# PowerSupply.net
KiCad netlist of a schematic drawn in Altium Designer
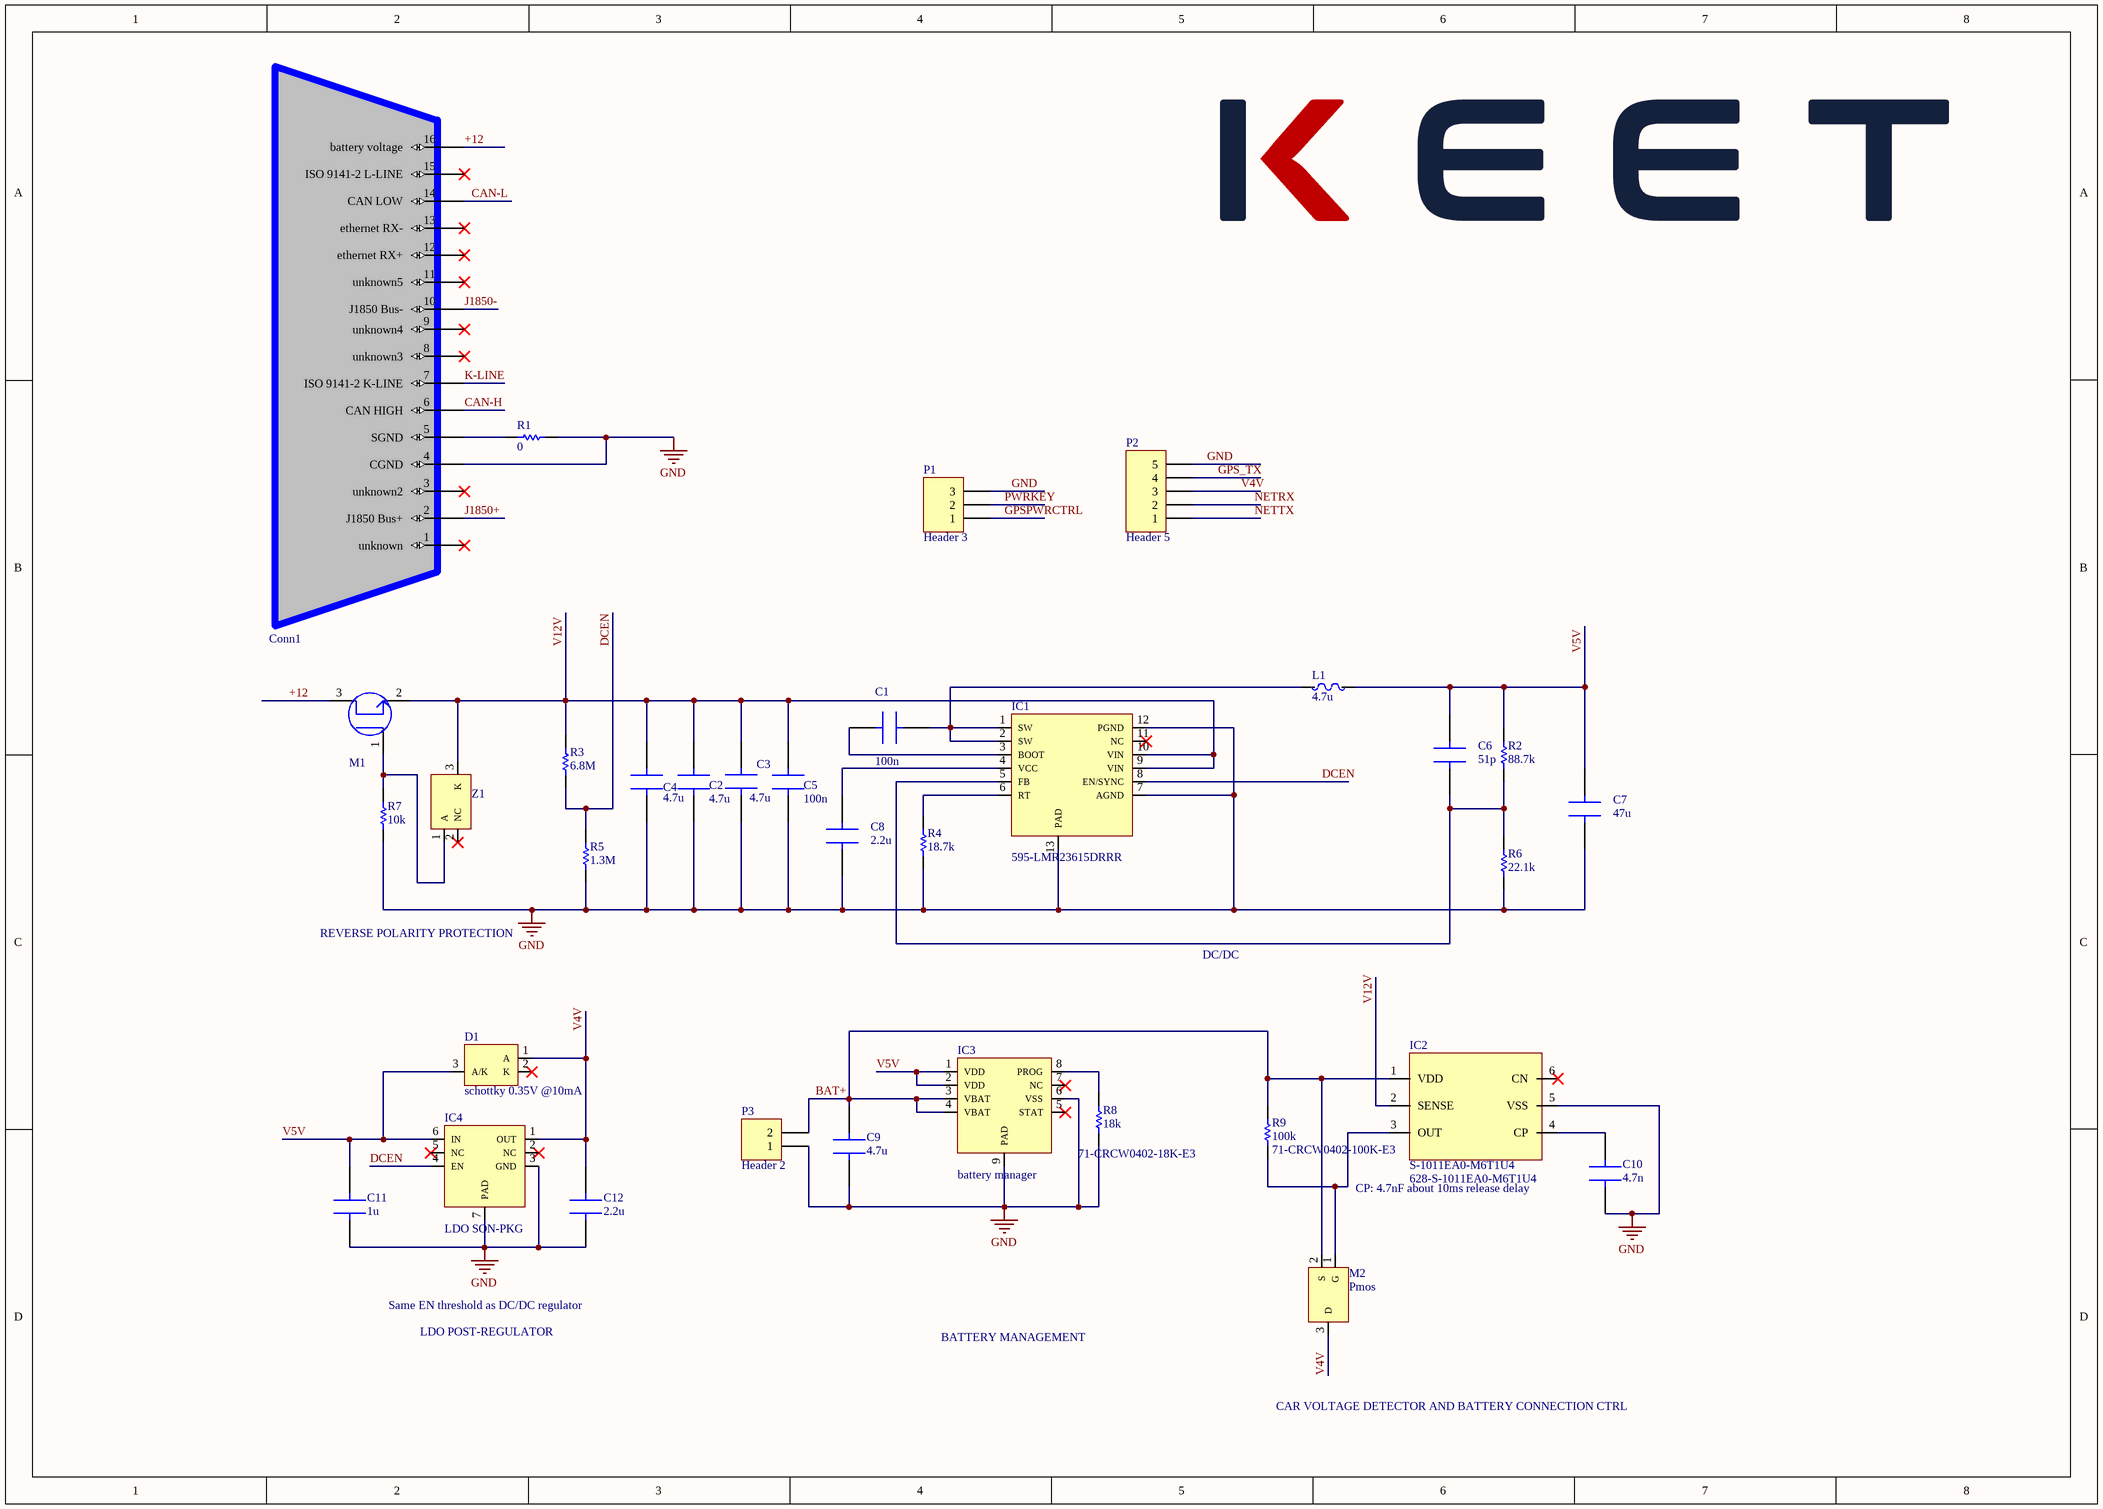
[diagram p0: PowerSupply.SchDoc]

(export (version "E")
  (design (tool "Eeschema 10.0.6"))
  (components
    (comp (ref "C1")
      (value "100n")
      (footprint "CAPC1005X06N")
      (description "CAP CER 0.1UF 16V X7R 0402")
      (fields
        (field (name "MANUFACTURER") "Murata")
        (field (name "MANUFACTURER PART NUMBER") "GRM155R71C104KA88D")
      )
      (libsource (lib "KeetV2") (part "GRM155R71C104KA88D"))
    )
    (comp (ref "C2")
      (value "4.7u")
      (footprint "CAPC1608X10N")
      (description "Cap Ceramic 4.7uF 25V X5R 20% SMD 0603 85°C Paper T/R")
      (fields
        (field (name "MANUFACTURER") "Taiyo Yuden")
        (field (name "MANUFACTURER PART NUMBER") "TMK107BBJ475MA-T")
      )
      (libsource (lib "KeetV2") (part "TMK107BBJ475MA-T"))
    )
    (comp (ref "C3")
      (value "4.7u")
      (footprint "CAPC1608X10N")
      (description "Cap Ceramic 4.7uF 25V X5R 20% SMD 0603 85°C Paper T/R")
      (fields
        (field (name "MANUFACTURER") "Taiyo Yuden")
        (field (name "MANUFACTURER PART NUMBER") "TMK107BBJ475MA-T")
      )
      (libsource (lib "KeetV2") (part "TMK107BBJ475MA-T"))
    )
    (comp (ref "C4")
      (value "4.7u")
      (footprint "CAPC1608X10N")
      (description "Cap Ceramic 4.7uF 25V X5R 20% SMD 0603 85°C Paper T/R")
      (fields
        (field (name "MANUFACTURER") "Taiyo Yuden")
        (field (name "MANUFACTURER PART NUMBER") "TMK107BBJ475MA-T")
      )
      (libsource (lib "KeetV2") (part "TMK107BBJ475MA-T"))
    )
    (comp (ref "C5")
      (value "100n")
      (footprint "CAPC1005X06N")
      (description "CAP CER 0.1UF 50V X5R 0402")
      (fields
        (field (name "MANUFACTURER") "TDK")
        (field (name "MANUFACTURER PART NUMBER") "C1005X5R1H104K050BB")
      )
      (libsource (lib "KeetV2") (part "C1005X5R1H104K050BB"))
    )
    (comp (ref "C6")
      (value "51p")
      (footprint "CAPC1005X06N")
      (description "CAP CER 51PF 50V C0G/NP0 0402")
      (fields
        (field (name "MANUFACTURER") "Murata")
        (field (name "MANUFACTURER PART NUMBER") "GRM1555C1H510JA01D")
      )
      (libsource (lib "KeetV2") (part "GRM1555C1H510JA01D"))
    )
    (comp (ref "C7")
      (value "47u")
      (footprint "CAPC3216X12N")
      (description "Multilayer Ceramic Capacitors MLCC - SMD/SMT 1206 47uF 10Vdc X5R +/-10%")
      (fields
        (field (name "MANUFACTURER") "Murata")
        (field (name "MANUFACTURER PART NUMBER") "GRM31CR61A476KE15L")
      )
      (libsource (lib "KeetV2") (part "GRM31CR61A476KE15L"))
    )
    (comp (ref "C8")
      (value "2.2u")
      (footprint "CAPC1608X10N")
      (fields
        (field (name "MANUFACTURER") "Samsung")
        (field (name "MANUFACTURER PART NUMBER") "CL10A225KP8NNNC")
        (field (name "TOLERANCE") "10%")
      )
      (libsource (lib "KeetV2") (part "CL10A225KP8NNNC"))
    )
    (comp (ref "C9")
      (value "4.7u")
      (footprint "CAPC1005X06N")
      (fields
        (field (name "MANUFACTURER") "Murata")
        (field (name "MANUFACTURER PART NUMBER") "GRM155R60J475ME87D")
        (field (name "TOLERANCE") "20%")
      )
      (libsource (lib "KeetV2") (part "GRM155R60J475ME87D"))
    )
    (comp (ref "C10")
      (value "4.7n")
      (footprint "CAPC1005X06N")
      (description "Multilayer Ceramic Capacitors MLCC - SMD/SMT")
      (fields
        (field (name "MANUFACTURER") "Murata")
        (field (name "MANUFACTURER PART NUMBER") "GRM155R71H472JA01J")
      )
      (libsource (lib "KeetV2") (part "GRM155R71H472JA01J"))
    )
    (comp (ref "C11")
      (value "1u")
      (footprint "CAPC1005X06N")
      (description "TAIYO YUDEN - EMK105BJ105KVHF - CAPACITOR,CERAMIC,0402,16V,X5R,1 F, 10% ROHS COMPLIANT: YES")
      (fields
        (field (name "MANUFACTURER") "Taiyo Yuden")
        (field (name "MANUFACTURER PART NUMBER") "EMK105BJ105KVHF")
      )
      (libsource (lib "KeetV2") (part "EMK105BJ105KVHF"))
    )
    (comp (ref "C12")
      (value "2.2u")
      (footprint "CAPC1005X06N")
      (description "Multilayer Ceramic Capacitor 2.2uF 25V 10% 0402 Paper T/R")
      (fields
        (field (name "MANUFACTURER") "Taiyo Yuden")
        (field (name "MANUFACTURER PART NUMBER") "TMK105CBJ225KV-F")
      )
      (libsource (lib "KeetV2") (part "TMK105CBJ225KV-F"))
    )
    (comp (ref "Conn1")
      (value "OBD2 connector")
      (footprint "OBD2")
      (libsource (lib "KeetV2") (part "OBD2 connector"))
    )
    (comp (ref "D1")
      (value "schottky 0.35V @10mA")
      (footprint "SOT95P245X110-3N")
      (description "Diode Schottky 30V 0.2A 3-Pin SOT-23 T/R")
      (fields
        (field (name "MANUFACTURER") "ON Semiconductor")
        (field (name "MANUFACTURER PART NUMBER") "BAT54CLT1G")
      )
      (libsource (lib "KeetV2") (part "BAT54CLT1G"))
    )
    (comp (ref "IC1")
      (value "DC/DC")
      (footprint "SON50P300X80_HS-13N")
      (description "SIMPLE SWITCHER®, 36-V, 1.5-A Synchronous Step-Down Converter 12-SON -40 to 125")
      (fields
        (field (name "MANUFACTURER") "Texas Instruments")
        (field (name "MANUFACTURER PART NUMBER") "LMR23615DRRR")
        (field (name "SUPPLIER PART NUMBER 1") "595-LMR23615DRRR")
      )
      (libsource (lib "KeetV2") (part "LMR23615DRRR"))
    )
    (comp (ref "IC2")
      (value "S-1011EA0-M6T1U4")
      (footprint "SOT95P245X110-6N")
      (description "Voltage detector")
      (fields
        (field (name "MANUFACTURER") "ABLIC U.S.A.")
        (field (name "SUPPLIER PART NUMBER 1") "628-S-1011EA0-M6T1U4")
      )
      (libsource (lib "KeetV2") (part "S-1011EA0-M6T1U4"))
    )
    (comp (ref "IC3")
      (value "battery manager")
      (footprint "PSON50P300X100_HS-9N")
      (description "IC CONTROLLER LI-ION 4.2V 8DFN")
      (fields
        (field (name "MANUFACTURER") "Microchip")
        (field (name "MANUFACTURER PART NUMBER") "MCP73831T-2ACI/MC")
      )
      (libsource (lib "KeetV2") (part "MCP73831T-2ACI/MC"))
    )
    (comp (ref "IC4")
      (value "LDO SON-PKG")
      (footprint "SON65P200X80_HS-7N")
      (description "1-A, low-IQ, high-accuracy, low-dropout voltage regulator with enable 6-WSON -40 to 125")
      (fields
        (field (name "MANUFACTURER") "Texas Instruments")
        (field (name "MANUFACTURER PART NUMBER") "TLV75740PDRVR")
      )
      (libsource (lib "KeetV2") (part "TLV75740PDRVR"))
    )
    (comp (ref "L1")
      (value "4.7u")
      (footprint "INDC4040X19N")
      (description "Inductor Power Shielded Wirewound 4.7uH 20% 100KHz 2.2A 90mOhm DCR 1515 T/R")
      (fields
        (field (name "MANUFACTURER") "Vishay Dale")
        (field (name "MANUFACTURER PART NUMBER") "IFSC1515AHER4R7M01")
      )
      (libsource (lib "KeetV2") (part "IFSC1515AHER4R7M01"))
    )
    (comp (ref "M1")
      (value "Pmos enhancement")
      (footprint "SOT95P245X110-3N")
      (description "DMPH6250SQ Series 60 V 2.4 A P-Channel Enhancement Mode Mosfet - SOT-23-3")
      (fields (field (name "MANUFACTURER") "Diodes") (field (name "MANUFACTURER PART NUMBER") "DMPH6250SQ-7"))
      (libsource (lib "KeetV2") (part "DMPH6250SQ-7"))
    )
    (comp (ref "M2")
      (value "Pmos")
      (footprint "SOT95P245X110-3N")
      (description "P-Channel 12 V 31 mOhm Surface Mount Enhancement Mode Mosfet - SOT-23-3")
      (fields (field (name "MANUFACTURER") "Diodes") (field (name "MANUFACTURER PART NUMBER") "DMP1045U-7"))
      (libsource (lib "KeetV2") (part "DMP1045U-7"))
    )
    (comp (ref "P1")
      (value "Header 3")
      (footprint "HDR1X3")
      (description "Header, 3-Pin")
      (fields (field (name "PUBLISHER") "Altium Limited"))
      (libsource (lib "Miscellaneous Connectors") (part "Header 3"))
    )
    (comp (ref "P2")
      (value "Header 5")
      (footprint "HDR1X5")
      (description "Header, 5-Pin")
      (fields (field (name "PUBLISHER") "Altium Limited"))
      (libsource (lib "Miscellaneous Connectors") (part "Header 5"))
    )
    (comp (ref "P3")
      (value "Header 2")
      (footprint "HDR1X2")
      (description "Header, 2-Pin")
      (fields (field (name "PUBLISHER") "Altium Limited"))
      (libsource (lib "Miscellaneous Connectors") (part "Header 2"))
    )
    (comp (ref "R1")
      (value "0")
      (footprint "RESC1608X04N")
      (description "YAGEO - RC0603JR-130RL - RES, THICK FILM, 0R, 0.1W, 0603")
      (fields
        (field (name "MANUFACTURER") "Yageo")
        (field (name "MANUFACTURER PART NUMBER") "RC0603JR-130RL")
      )
      (libsource (lib "KeetV2") (part "RC0603JR-130RL"))
    )
    (comp (ref "R2")
      (value "88.7k")
      (footprint "RESC1005X04N")
      (description "Res Thick Film 0402 88.7K Ohm 1% 0.063W(1/16W) ±100ppm/C Molded SMD Paper Tape on Plastic Reel")
      (fields
        (field (name "MANUFACTURER") "Bourns")
        (field (name "MANUFACTURER PART NUMBER") "CR0402-FX-8872GLF")
      )
      (libsource (lib "KeetV2") (part "CR0402-FX-8872GLF"))
    )
    (comp (ref "R3")
      (value "6.8M")
      (footprint "RESC1005X04N")
      (fields
        (field (name "MANUFACTURER") "Vishay")
        (field (name "MANUFACTURER PART NUMBER") "CRCW04026M80FKED")
        (field (name "TOLERANCE") "1%")
      )
      (libsource (lib "KeetV2") (part "CRCW04026M80FKED"))
    )
    (comp (ref "R4")
      (value "18.7k")
      (footprint "RESC1005X04N")
      (description "RES SMD 18.7K OHM 1% 1/16W 0402")
      (fields
        (field (name "MANUFACTURER") "Bourns")
        (field (name "MANUFACTURER PART NUMBER") "CR0402-FX-1872GLF")
      )
      (libsource (lib "KeetV2") (part "CR0402-FX-1872GLF"))
    )
    (comp (ref "R5")
      (value "1.3M")
      (footprint "RESC1005X04N")
      (description "RES SMD 1.3M OHM 1% 1/16W 0402")
      (fields
        (field (name "MANUFACTURER") "Yageo")
        (field (name "MANUFACTURER PART NUMBER") "AC0402FR-071M3L")
      )
      (libsource (lib "KeetV2") (part "AC0402FR-071M3L"))
    )
    (comp (ref "R6")
      (value "22.1k")
      (footprint "RESC1005X04N")
      (description "Resistor;  Thick Film;  22.1 Kilohms;  0.063 W;  1%;  SMT;  0402;  TCR 37 ppm/DegC;  TR")
      (fields
        (field (name "MANUFACTURER") "Vishay")
        (field (name "MANUFACTURER PART NUMBER") "CRCW040222K1FKED")
      )
      (libsource (lib "KeetV2") (part "CRCW040222K1FKED"))
    )
    (comp (ref "R7")
      (value "10k")
      (footprint "RESC1005X04N")
      (description "Res Thick Film 0402 10K Ohm 1% 1/16W ±100ppm/°C Molded SMD Paper T/R")
      (fields
        (field (name "MANUFACTURER") "Vishay")
        (field (name "MANUFACTURER PART NUMBER") "CRCW0402-10K0FKED")
      )
      (libsource (lib "KeetV2") (part "CRCW0402-10K0FKED"))
    )
    (comp (ref "R8")
      (value "18k")
      (footprint "RESC1005X04N")
      (fields
        (field (name "MANUFACTURER") "Vishay")
        (field (name "MANUFACTURER PART NUMBER") "CRCW040218K0FKED")
        (field (name "TOLERANCE") "1%")
        (field (name "SUPPLIER PART NUMBER 1") "71-CRCW0402-18K-E3")
      )
      (libsource (lib "KeetV2") (part "CRCW040218K0FKED"))
    )
    (comp (ref "R9")
      (value "100k")
      (footprint "RESC1005X04N")
      (description "Res Thick Film 0402 100K Ohm 1% 1/16W 100ppm/C Molded SMD Paper T/R")
      (fields
        (field (name "MANUFACTURER") "Vishay")
        (field (name "MANUFACTURER PART NUMBER") "CRCW0402100KFKED")
        (field (name "SUPPLIER PART NUMBER 1") "71-CRCW0402-100K-E3")
      )
      (libsource (lib "KeetV2") (part "CRCW0402100KFKED"))
    )
    (comp (ref "Z1")
      (value "zener 10V")
      (footprint "SOT95P245X110-3N")
      (description "ON SEMICONDUCTOR - BZX84C10LT1G - Zener Single Diode, 10 V, 225 mW, SOT-23, 6 %, 3 Pins, 150 °C")
      (fields
        (field (name "MANUFACTURER") "ON Semiconductor")
        (field (name "MANUFACTURER PART NUMBER") "BZX84C10LT1G")
      )
      (libsource (lib "KeetV2") (part "BZX84C10LT1G"))
    )
  )
  (nets
    (net (code "1") (name "/+12") (class "Default")
      (node (ref "Conn1") (pin "16") (pinfunction "battery_voltage_16") (pintype "bidirectional"))
      (node (ref "M1") (pin "3") (pinfunction "3_3") (pintype "passive"))
    )
    (net (code "2") (name "/BAT+") (class "Default")
      (node (ref "C9") (pin "2") (pinfunction "2_2") (pintype "passive"))
      (node (ref "IC2") (pin "1") (pinfunction "VDD_1") (pintype "passive"))
      (node (ref "IC3") (pin "3") (pinfunction "VBAT_3") (pintype "passive"))
      (node (ref "IC3") (pin "4") (pinfunction "VBAT_4") (pintype "passive"))
      (node (ref "M2") (pin "2") (pinfunction "S_2") (pintype "passive"))
      (node (ref "P3") (pin "2") (pinfunction "2_2") (pintype "passive"))
      (node (ref "R9") (pin "1") (pinfunction "1_1") (pintype "passive"))
    )
    (net (code "3") (name "/CAN-H") (class "Default")
      (node (ref "Conn1") (pin "6") (pinfunction "CAN_HIGH_6") (pintype "bidirectional"))
    )
    (net (code "4") (name "/CAN-L") (class "Default")
      (node (ref "Conn1") (pin "14") (pinfunction "CAN_LOW_14") (pintype "bidirectional"))
    )
    (net (code "5") (name "/DCEN") (class "Default")
      (node (ref "IC1") (pin "8") (pinfunction "EN/SYNC_8") (pintype "passive"))
      (node (ref "IC4") (pin "4") (pinfunction "EN_4") (pintype "passive"))
      (node (ref "R3") (pin "1") (pinfunction "1_1") (pintype "passive"))
      (node (ref "R5") (pin "2") (pinfunction "2_2") (pintype "passive"))
    )
    (net (code "6") (name "/GPSPWRCTRL") (class "Default")
      (node (ref "P1") (pin "1") (pinfunction "1_1") (pintype "passive"))
    )
    (net (code "7") (name "/GPS_TX") (class "Default")
      (node (ref "P2") (pin "4") (pinfunction "4_4") (pintype "passive"))
    )
    (net (code "8") (name "/J1850+") (class "Default")
      (node (ref "Conn1") (pin "2") (pinfunction "J1850_Bus+_2") (pintype "bidirectional"))
    )
    (net (code "9") (name "/J1850-") (class "Default")
      (node (ref "Conn1") (pin "10") (pinfunction "J1850_Bus-_10") (pintype "bidirectional"))
    )
    (net (code "10") (name "/K-LINE") (class "Default")
      (node (ref "Conn1") (pin "7") (pinfunction "ISO_9141-2_K-LINE_7") (pintype "bidirectional"))
    )
    (net (code "11") (name "/NETRX") (class "Default")
      (node (ref "P2") (pin "2") (pinfunction "2_2") (pintype "passive"))
    )
    (net (code "12") (name "/NETTX") (class "Default")
      (node (ref "P2") (pin "1") (pinfunction "1_1") (pintype "passive"))
    )
    (net (code "13") (name "/PWRKEY") (class "Default")
      (node (ref "P1") (pin "2") (pinfunction "2_2") (pintype "passive"))
    )
    (net (code "14") (name "/V4V") (class "Default")
      (node (ref "C12") (pin "1") (pinfunction "1_1") (pintype "passive"))
      (node (ref "D1") (pin "1") (pinfunction "A_1") (pintype "passive"))
      (node (ref "IC4") (pin "1") (pinfunction "OUT_1") (pintype "passive"))
      (node (ref "M2") (pin "3") (pinfunction "D_3") (pintype "passive"))
      (node (ref "P2") (pin "3") (pinfunction "3_3") (pintype "passive"))
    )
    (net (code "15") (name "/V5V") (class "Default")
      (node (ref "C11") (pin "1") (pinfunction "1_1") (pintype "passive"))
      (node (ref "C6") (pin "2") (pinfunction "2_2") (pintype "passive"))
      (node (ref "C7") (pin "2") (pinfunction "2_2") (pintype "passive"))
      (node (ref "D1") (pin "3") (pinfunction "A/K_3") (pintype "passive"))
      (node (ref "IC3") (pin "1") (pinfunction "VDD_1") (pintype "passive"))
      (node (ref "IC3") (pin "2") (pinfunction "VDD_2") (pintype "passive"))
      (node (ref "IC4") (pin "6") (pinfunction "IN_6") (pintype "passive"))
      (node (ref "L1") (pin "2") (pinfunction "2_2") (pintype "passive"))
      (node (ref "R2") (pin "2") (pinfunction "2_2") (pintype "passive"))
    )
    (net (code "16") (name "/V12V") (class "Default")
      (node (ref "C2") (pin "2") (pinfunction "2_2") (pintype "passive"))
      (node (ref "C3") (pin "1") (pinfunction "1_1") (pintype "passive"))
      (node (ref "C4") (pin "2") (pinfunction "2_2") (pintype "passive"))
      (node (ref "C5") (pin "2") (pinfunction "2_2") (pintype "passive"))
      (node (ref "IC1") (pin "10") (pinfunction "VIN_10") (pintype "passive"))
      (node (ref "IC1") (pin "9") (pinfunction "VIN_9") (pintype "passive"))
      (node (ref "IC2") (pin "2") (pinfunction "SENSE_2") (pintype "passive"))
      (node (ref "M1") (pin "2") (pinfunction "2_2") (pintype "passive"))
      (node (ref "R3") (pin "2") (pinfunction "2_2") (pintype "passive"))
      (node (ref "Z1") (pin "3") (pinfunction "K_3") (pintype "passive"))
    )
    (net (code "17") (name "GND") (class "Default")
      (node (ref "C10") (pin "1") (pinfunction "1_1") (pintype "passive"))
      (node (ref "C11") (pin "2") (pinfunction "2_2") (pintype "passive"))
      (node (ref "C12") (pin "2") (pinfunction "2_2") (pintype "passive"))
      (node (ref "C2") (pin "1") (pinfunction "1_1") (pintype "passive"))
      (node (ref "C3") (pin "2") (pinfunction "2_2") (pintype "passive"))
      (node (ref "C4") (pin "1") (pinfunction "1_1") (pintype "passive"))
      (node (ref "C5") (pin "1") (pinfunction "1_1") (pintype "passive"))
      (node (ref "C7") (pin "1") (pinfunction "1_1") (pintype "passive"))
      (node (ref "C8") (pin "1") (pinfunction "1_1") (pintype "passive"))
      (node (ref "C9") (pin "1") (pinfunction "1_1") (pintype "passive"))
      (node (ref "Conn1") (pin "4") (pinfunction "CGND_4") (pintype "bidirectional"))
      (node (ref "IC1") (pin "12") (pinfunction "PGND_12") (pintype "passive"))
      (node (ref "IC1") (pin "13") (pinfunction "PAD_13") (pintype "passive"))
      (node (ref "IC1") (pin "7") (pinfunction "AGND_7") (pintype "passive"))
      (node (ref "IC2") (pin "5") (pinfunction "VSS_5") (pintype "passive"))
      (node (ref "IC3") (pin "6") (pinfunction "VSS_6") (pintype "passive"))
      (node (ref "IC3") (pin "9") (pinfunction "PAD_9") (pintype "passive"))
      (node (ref "IC4") (pin "3") (pinfunction "GND_3") (pintype "passive"))
      (node (ref "IC4") (pin "7") (pinfunction "PAD_7") (pintype "passive"))
      (node (ref "P1") (pin "3") (pinfunction "3_3") (pintype "passive"))
      (node (ref "P2") (pin "5") (pinfunction "5_5") (pintype "passive"))
      (node (ref "P3") (pin "1") (pinfunction "1_1") (pintype "passive"))
      (node (ref "R1") (pin "2") (pinfunction "2_2") (pintype "passive"))
      (node (ref "R4") (pin "1") (pinfunction "1_1") (pintype "passive"))
      (node (ref "R5") (pin "1") (pinfunction "1_1") (pintype "passive"))
      (node (ref "R6") (pin "1") (pinfunction "1_1") (pintype "passive"))
      (node (ref "R7") (pin "1") (pinfunction "1_1") (pintype "passive"))
      (node (ref "R8") (pin "1") (pinfunction "1_1") (pintype "passive"))
    )
    (net (code "18") (name "Net-(C1-Pad2)") (class "Default")
      (node (ref "C1") (pin "2") (pinfunction "2_2") (pintype "passive"))
      (node (ref "IC1") (pin "1") (pinfunction "SW_1") (pintype "passive"))
      (node (ref "IC1") (pin "2") (pinfunction "SW_2") (pintype "passive"))
      (node (ref "L1") (pin "1") (pinfunction "1_1") (pintype "passive"))
    )
    (net (code "19") (name "Net-(Conn1-SGND)") (class "Default")
      (node (ref "Conn1") (pin "5") (pinfunction "SGND_5") (pintype "bidirectional"))
      (node (ref "R1") (pin "1") (pinfunction "1_1") (pintype "passive"))
    )
    (net (code "20") (name "Net-(IC1-BOOT)") (class "Default")
      (node (ref "C1") (pin "1") (pinfunction "1_1") (pintype "passive"))
      (node (ref "IC1") (pin "3") (pinfunction "BOOT_3") (pintype "passive"))
    )
    (net (code "21") (name "Net-(IC1-FB)") (class "Default")
      (node (ref "C6") (pin "1") (pinfunction "1_1") (pintype "passive"))
      (node (ref "IC1") (pin "5") (pinfunction "FB_5") (pintype "passive"))
      (node (ref "R2") (pin "1") (pinfunction "1_1") (pintype "passive"))
      (node (ref "R6") (pin "2") (pinfunction "2_2") (pintype "passive"))
    )
    (net (code "22") (name "Net-(IC1-RT)") (class "Default")
      (node (ref "IC1") (pin "6") (pinfunction "RT_6") (pintype "passive"))
      (node (ref "R4") (pin "2") (pinfunction "2_2") (pintype "passive"))
    )
    (net (code "23") (name "Net-(IC1-VCC)") (class "Default")
      (node (ref "C8") (pin "2") (pinfunction "2_2") (pintype "passive"))
      (node (ref "IC1") (pin "4") (pinfunction "VCC_4") (pintype "passive"))
    )
    (net (code "24") (name "Net-(IC2-CP)") (class "Default")
      (node (ref "C10") (pin "2") (pinfunction "2_2") (pintype "passive"))
      (node (ref "IC2") (pin "4") (pinfunction "CP_4") (pintype "passive"))
    )
    (net (code "25") (name "Net-(IC2-OUT)") (class "Default")
      (node (ref "IC2") (pin "3") (pinfunction "OUT_3") (pintype "passive"))
      (node (ref "M2") (pin "1") (pinfunction "G_1") (pintype "passive"))
      (node (ref "R9") (pin "2") (pinfunction "2_2") (pintype "passive"))
    )
    (net (code "26") (name "Net-(IC3-PROG)") (class "Default")
      (node (ref "IC3") (pin "8") (pinfunction "PROG_8") (pintype "passive"))
      (node (ref "R8") (pin "2") (pinfunction "2_2") (pintype "passive"))
    )
    (net (code "27") (name "Net-(Z1-A)") (class "Default")
      (node (ref "M1") (pin "1") (pinfunction "1_1") (pintype "passive"))
      (node (ref "R7") (pin "2") (pinfunction "2_2") (pintype "passive"))
      (node (ref "Z1") (pin "1") (pinfunction "A_1") (pintype "passive"))
    )
    (net (code "28") (name "unconnected-(Conn1-ISO_9141-2_L-LINE-Pad15)") (class "Default")
      (node (ref "Conn1") (pin "15") (pinfunction "ISO_9141-2_L-LINE_15") (pintype "bidirectional+no_connect"))
    )
    (net (code "29") (name "unconnected-(Conn1-ethernet_RX+-Pad12)") (class "Default")
      (node (ref "Conn1") (pin "12") (pinfunction "ethernet_RX+_12") (pintype "bidirectional+no_connect"))
    )
    (net (code "30") (name "unconnected-(Conn1-ethernet_RX--Pad13)") (class "Default")
      (node (ref "Conn1") (pin "13") (pinfunction "ethernet_RX-_13") (pintype "bidirectional+no_connect"))
    )
    (net (code "31") (name "unconnected-(Conn1-unknown-Pad1)") (class "Default")
      (node (ref "Conn1") (pin "1") (pinfunction "unknown_1") (pintype "bidirectional+no_connect"))
    )
    (net (code "32") (name "unconnected-(Conn1-unknown2-Pad3)") (class "Default")
      (node (ref "Conn1") (pin "3") (pinfunction "unknown2_3") (pintype "bidirectional+no_connect"))
    )
    (net (code "33") (name "unconnected-(Conn1-unknown3-Pad8)") (class "Default")
      (node (ref "Conn1") (pin "8") (pinfunction "unknown3_8") (pintype "bidirectional+no_connect"))
    )
    (net (code "34") (name "unconnected-(Conn1-unknown4-Pad9)") (class "Default")
      (node (ref "Conn1") (pin "9") (pinfunction "unknown4_9") (pintype "bidirectional+no_connect"))
    )
    (net (code "35") (name "unconnected-(Conn1-unknown5-Pad11)") (class "Default")
      (node (ref "Conn1") (pin "11") (pinfunction "unknown5_11") (pintype "bidirectional+no_connect"))
    )
    (net (code "36") (name "unconnected-(D1-K-Pad2)") (class "Default")
      (node (ref "D1") (pin "2") (pinfunction "K_2") (pintype "passive+no_connect"))
    )
    (net (code "37") (name "unconnected-(IC1-NC-Pad11)") (class "Default")
      (node (ref "IC1") (pin "11") (pinfunction "NC_11") (pintype "passive+no_connect"))
    )
    (net (code "38") (name "unconnected-(IC2-CN-Pad6)") (class "Default")
      (node (ref "IC2") (pin "6") (pinfunction "CN_6") (pintype "passive+no_connect"))
    )
    (net (code "39") (name "unconnected-(IC3-NC-Pad7)") (class "Default")
      (node (ref "IC3") (pin "7") (pinfunction "NC_7") (pintype "passive+no_connect"))
    )
    (net (code "40") (name "unconnected-(IC3-STAT-Pad5)") (class "Default")
      (node (ref "IC3") (pin "5") (pinfunction "STAT_5") (pintype "passive+no_connect"))
    )
    (net (code "41") (name "unconnected-(IC4-NC-Pad2)") (class "Default")
      (node (ref "IC4") (pin "2") (pinfunction "NC_2") (pintype "passive+no_connect"))
    )
    (net (code "42") (name "unconnected-(IC4-NC-Pad5)") (class "Default")
      (node (ref "IC4") (pin "5") (pinfunction "NC_5") (pintype "passive+no_connect"))
    )
    (net (code "43") (name "unconnected-(Z1-NC-Pad2)") (class "Default")
      (node (ref "Z1") (pin "2") (pinfunction "NC_2") (pintype "passive+no_connect"))
    )
  )
)
